# talking_train.net
KiCad netlist of a schematic drawn in EasyEDA Pro
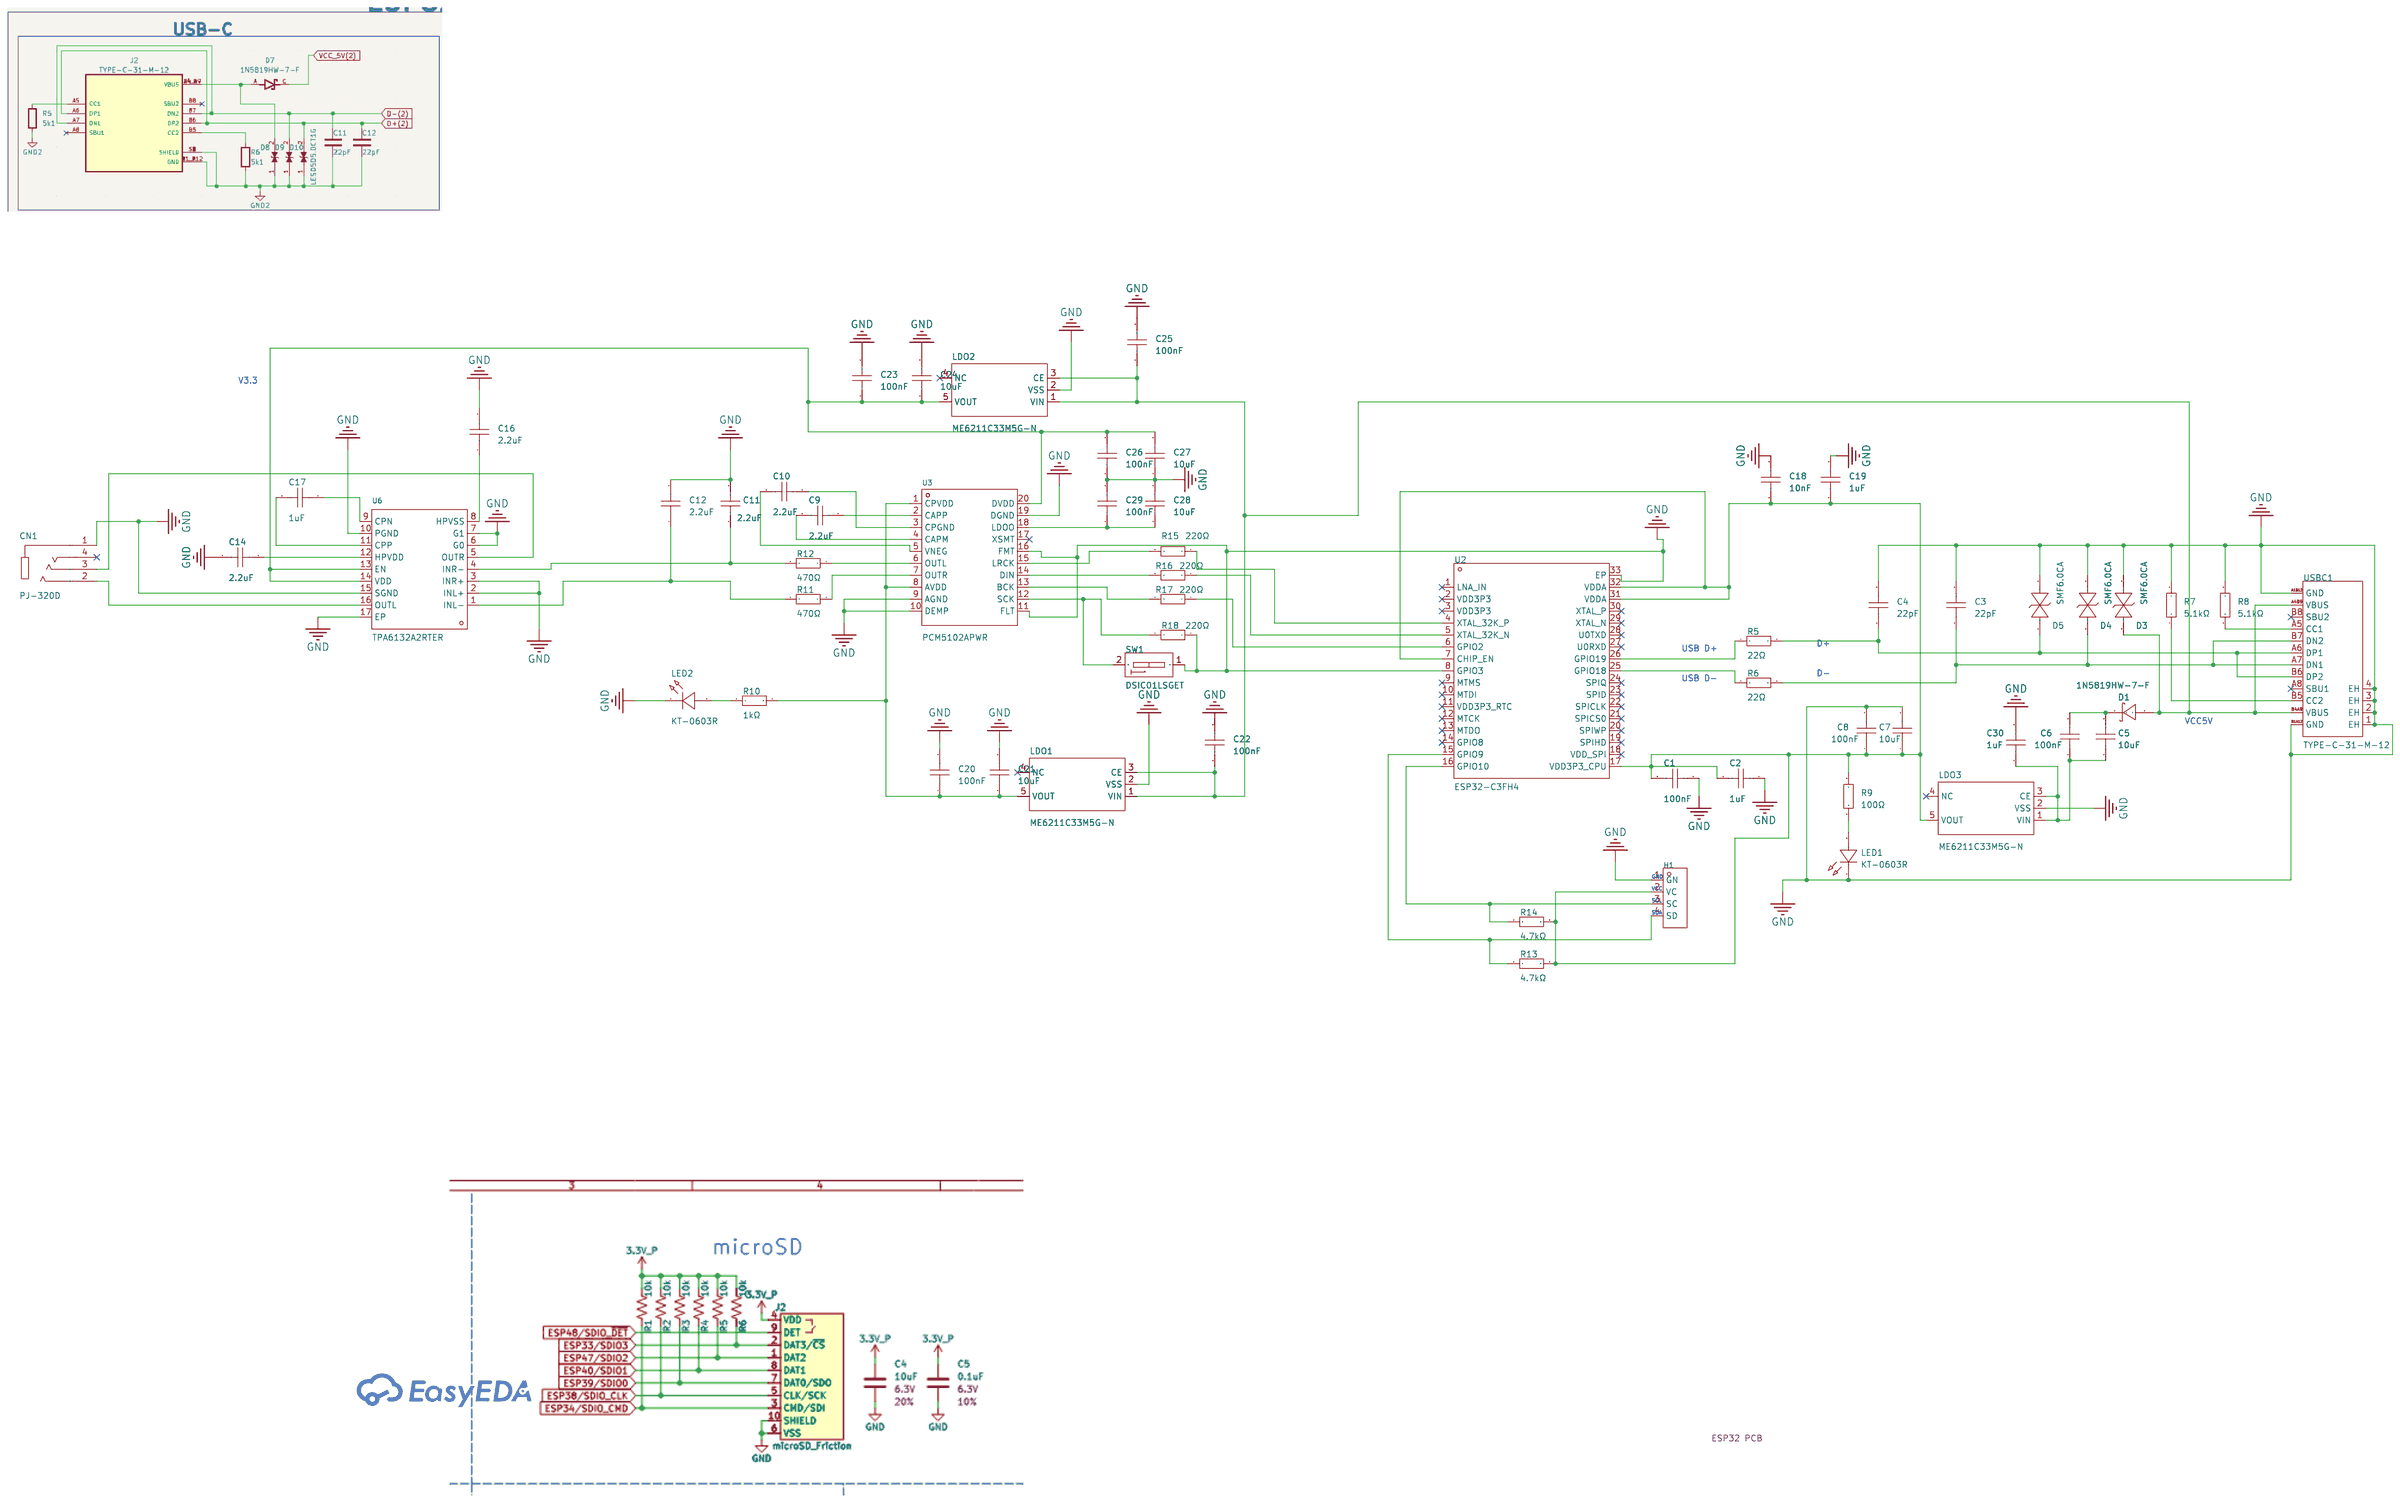
[diagram p0: schematic sheet]

(export (version "E")
  (design (tool "Eeschema 10.0.6"))
  (components
    (comp (ref "C1")
      (value "100nF")
      (footprint "easyedapro:C0603")
      (description "Capacitance:100nF Tolerance:±10% Tolerance:±10% Voltage Rating:50V Temperature Coefficient:X7R")
      (fields
        (field (name "Manufacturer Part") "CC0603KRX7R9BB104")
        (field (name "Manufacturer") "YAGEO(国巨)")
      )
      (libsource (lib "easyedapro") (part "CAP"))
    )
    (comp (ref "C2")
      (value "1uF")
      (footprint "easyedapro:C0603")
      (description "Capacitance:1uF Tolerance:±10% Tolerance:±10% Voltage Rating:50V Temperature Coefficient:X5R")
      (fields
        (field (name "Manufacturer Part") "CL10A105KB8NNNC")
        (field (name "Manufacturer") "SAMSUNG(三星)")
      )
      (libsource (lib "easyedapro") (part "CAP"))
    )
    (comp (ref "C3")
      (value "22pF")
      (footprint "easyedapro:C0603")
      (description "Capacitance:22pF Tolerance:±5% Tolerance:±5% Voltage Rating:50V Temperature Coefficient:C0G")
      (fields
        (field (name "Manufacturer Part") "CL10C220JB8NNNC")
        (field (name "Manufacturer") "SAMSUNG(三星)")
      )
      (libsource (lib "easyedapro") (part "CAP"))
    )
    (comp (ref "C4")
      (value "22pF")
      (footprint "easyedapro:C0603")
      (description "Capacitance:22pF Tolerance:±5% Tolerance:±5% Voltage Rating:50V Temperature Coefficient:C0G")
      (fields
        (field (name "Manufacturer Part") "CL10C220JB8NNNC")
        (field (name "Manufacturer") "SAMSUNG(三星)")
      )
      (libsource (lib "easyedapro") (part "CAP"))
    )
    (comp (ref "C5")
      (value "10uF")
      (footprint "easyedapro:C0603")
      (description "Capacitance:10uF Tolerance:±10% Tolerance:±10% Voltage Rating:10V Temperature Coefficient:X5R")
      (fields
        (field (name "Manufacturer Part") "CL10A106KP8NNNC")
        (field (name "Manufacturer") "SAMSUNG(三星)")
      )
      (libsource (lib "easyedapro") (part "CAP"))
    )
    (comp (ref "C6")
      (value "100nF")
      (footprint "easyedapro:C0603")
      (description "Capacitance:100nF Tolerance:±10% Tolerance:±10% Voltage Rating:50V Temperature Coefficient:X7R")
      (fields
        (field (name "Manufacturer Part") "CC0603KRX7R9BB104")
        (field (name "Manufacturer") "YAGEO(国巨)")
      )
      (libsource (lib "easyedapro") (part "CAP"))
    )
    (comp (ref "C7")
      (value "10uF")
      (footprint "easyedapro:C0603")
      (description "Capacitance:10uF Tolerance:±10% Tolerance:±10% Voltage Rating:10V Temperature Coefficient:X5R")
      (fields
        (field (name "Manufacturer Part") "CL10A106KP8NNNC")
        (field (name "Manufacturer") "SAMSUNG(三星)")
      )
      (libsource (lib "easyedapro") (part "CAP"))
    )
    (comp (ref "C8")
      (value "100nF")
      (footprint "easyedapro:C0603")
      (description "Capacitance:100nF Tolerance:±10% Tolerance:±10% Voltage Rating:50V Temperature Coefficient:X7R")
      (fields
        (field (name "Manufacturer Part") "CC0603KRX7R9BB104")
        (field (name "Manufacturer") "YAGEO(国巨)")
      )
      (libsource (lib "easyedapro") (part "CAP"))
    )
    (comp (ref "C9")
      (value "2.2uF")
      (footprint "easyedapro:C0603")
      (description "Capacitance:2.2uF Tolerance:±10% Tolerance:±10% Voltage Rating:16V Temperature Coefficient:X5R")
      (fields
        (field (name "Manufacturer Part") "CL10A225KO8NNNC")
        (field (name "Manufacturer") "SAMSUNG(三星)")
      )
      (libsource (lib "easyedapro") (part "CAP"))
    )
    (comp (ref "C10")
      (value "2.2uF")
      (footprint "easyedapro:C0603")
      (description "Capacitance:2.2uF Tolerance:±10% Tolerance:±10% Voltage Rating:16V Temperature Coefficient:X5R")
      (fields
        (field (name "Manufacturer Part") "CL10A225KO8NNNC")
        (field (name "Manufacturer") "SAMSUNG(三星)")
      )
      (libsource (lib "easyedapro") (part "CAP"))
    )
    (comp (ref "C11")
      (value "2.2uF")
      (footprint "easyedapro:C0603")
      (description "Capacitance:2.2uF Tolerance:±10% Tolerance:±10% Voltage Rating:16V Temperature Coefficient:X5R")
      (fields
        (field (name "Manufacturer Part") "CL10A225KO8NNNC")
        (field (name "Manufacturer") "SAMSUNG(三星)")
      )
      (libsource (lib "easyedapro") (part "CAP"))
    )
    (comp (ref "C12")
      (value "2.2uF")
      (footprint "easyedapro:C0603")
      (description "Capacitance:2.2uF Tolerance:±10% Tolerance:±10% Voltage Rating:16V Temperature Coefficient:X5R")
      (fields
        (field (name "Manufacturer Part") "CL10A225KO8NNNC")
        (field (name "Manufacturer") "SAMSUNG(三星)")
      )
      (libsource (lib "easyedapro") (part "CAP"))
    )
    (comp (ref "C14")
      (value "2.2uF")
      (footprint "easyedapro:C0603")
      (description "Capacitance:2.2uF Tolerance:±10% Tolerance:±10% Voltage Rating:16V Temperature Coefficient:X5R")
      (fields
        (field (name "Manufacturer Part") "CL10A225KO8NNNC")
        (field (name "Manufacturer") "SAMSUNG(三星)")
      )
      (libsource (lib "easyedapro") (part "CAP"))
    )
    (comp (ref "C16")
      (value "2.2uF")
      (footprint "easyedapro:C0603")
      (description "Capacitance:2.2uF Tolerance:±10% Tolerance:±10% Voltage Rating:16V Temperature Coefficient:X5R")
      (fields
        (field (name "Manufacturer Part") "CL10A225KO8NNNC")
        (field (name "Manufacturer") "SAMSUNG(三星)")
      )
      (libsource (lib "easyedapro") (part "CAP"))
    )
    (comp (ref "C17")
      (value "1uF")
      (footprint "easyedapro:C0603")
      (description "Capacitance:1uF Tolerance:±10% Tolerance:±10% Voltage Rating:50V Temperature Coefficient:X5R")
      (fields
        (field (name "Manufacturer Part") "CL10A105KB8NNNC")
        (field (name "Manufacturer") "SAMSUNG(三星)")
      )
      (libsource (lib "easyedapro") (part "CAP"))
    )
    (comp (ref "C18")
      (value "10nF")
      (footprint "easyedapro:C0603")
      (description "Capacitance:10nF Tolerance:±10% Tolerance:±10% Voltage Rating:50V Temperature Coefficient:X7R")
      (fields (field (name "Manufacturer Part") "0603B103K500NT") (field (name "Manufacturer") "FH(风华)"))
      (libsource (lib "easyedapro") (part "CAP"))
    )
    (comp (ref "C19")
      (value "1uF")
      (footprint "easyedapro:C0603")
      (description "Capacitance:1uF Tolerance:±10% Tolerance:±10% Voltage Rating:50V Temperature Coefficient:X5R")
      (fields
        (field (name "Manufacturer Part") "CL10A105KB8NNNC")
        (field (name "Manufacturer") "SAMSUNG(三星)")
      )
      (libsource (lib "easyedapro") (part "CAP"))
    )
    (comp (ref "C20")
      (value "100nF")
      (footprint "easyedapro:C0603")
      (description "Capacitance:100nF Tolerance:±10% Tolerance:±10% Voltage Rating:50V Temperature Coefficient:X7R")
      (fields
        (field (name "Manufacturer Part") "CC0603KRX7R9BB104")
        (field (name "Manufacturer") "YAGEO(国巨)")
      )
      (libsource (lib "easyedapro") (part "CAP"))
    )
    (comp (ref "C21")
      (value "10uF")
      (footprint "easyedapro:C0603")
      (description "Capacitance:10uF Tolerance:±10% Tolerance:±10% Voltage Rating:10V Temperature Coefficient:X5R")
      (fields
        (field (name "Manufacturer Part") "CL10A106KP8NNNC")
        (field (name "Manufacturer") "SAMSUNG(三星)")
      )
      (libsource (lib "easyedapro") (part "CAP"))
    )
    (comp (ref "C22")
      (value "100nF")
      (footprint "easyedapro:C0603")
      (description "Capacitance:100nF Tolerance:±10% Tolerance:±10% Voltage Rating:50V Temperature Coefficient:X7R")
      (fields
        (field (name "Manufacturer Part") "CC0603KRX7R9BB104")
        (field (name "Manufacturer") "YAGEO(国巨)")
      )
      (libsource (lib "easyedapro") (part "CAP"))
    )
    (comp (ref "C23")
      (value "100nF")
      (footprint "easyedapro:C0603")
      (description "Capacitance:100nF Tolerance:±10% Tolerance:±10% Voltage Rating:50V Temperature Coefficient:X7R")
      (fields
        (field (name "Manufacturer Part") "CC0603KRX7R9BB104")
        (field (name "Manufacturer") "YAGEO(国巨)")
      )
      (libsource (lib "easyedapro") (part "CAP"))
    )
    (comp (ref "C24")
      (value "10uF")
      (footprint "easyedapro:C0603")
      (description "Capacitance:10uF Tolerance:±10% Tolerance:±10% Voltage Rating:10V Temperature Coefficient:X5R")
      (fields
        (field (name "Manufacturer Part") "CL10A106KP8NNNC")
        (field (name "Manufacturer") "SAMSUNG(三星)")
      )
      (libsource (lib "easyedapro") (part "CAP"))
    )
    (comp (ref "C25")
      (value "100nF")
      (footprint "easyedapro:C0603")
      (description "Capacitance:100nF Tolerance:±10% Tolerance:±10% Voltage Rating:50V Temperature Coefficient:X7R")
      (fields
        (field (name "Manufacturer Part") "CC0603KRX7R9BB104")
        (field (name "Manufacturer") "YAGEO(国巨)")
      )
      (libsource (lib "easyedapro") (part "CAP"))
    )
    (comp (ref "C26")
      (value "100nF")
      (footprint "easyedapro:C0603")
      (description "Capacitance:100nF Tolerance:±10% Tolerance:±10% Voltage Rating:50V Temperature Coefficient:X7R")
      (fields
        (field (name "Manufacturer Part") "CC0603KRX7R9BB104")
        (field (name "Manufacturer") "YAGEO(国巨)")
      )
      (libsource (lib "easyedapro") (part "CAP"))
    )
    (comp (ref "C27")
      (value "10uF")
      (footprint "easyedapro:C0603")
      (description "Capacitance:10uF Tolerance:±10% Tolerance:±10% Voltage Rating:10V Temperature Coefficient:X5R")
      (fields
        (field (name "Manufacturer Part") "CL10A106KP8NNNC")
        (field (name "Manufacturer") "SAMSUNG(三星)")
      )
      (libsource (lib "easyedapro") (part "CAP"))
    )
    (comp (ref "C28")
      (value "10uF")
      (footprint "easyedapro:C0603")
      (description "Capacitance:10uF Tolerance:±10% Tolerance:±10% Voltage Rating:10V Temperature Coefficient:X5R")
      (fields
        (field (name "Manufacturer Part") "CL10A106KP8NNNC")
        (field (name "Manufacturer") "SAMSUNG(三星)")
      )
      (libsource (lib "easyedapro") (part "CAP"))
    )
    (comp (ref "C29")
      (value "100nF")
      (footprint "easyedapro:C0603")
      (description "Capacitance:100nF Tolerance:±10% Tolerance:±10% Voltage Rating:50V Temperature Coefficient:X7R")
      (fields
        (field (name "Manufacturer Part") "CC0603KRX7R9BB104")
        (field (name "Manufacturer") "YAGEO(国巨)")
      )
      (libsource (lib "easyedapro") (part "CAP"))
    )
    (comp (ref "C30")
      (value "1uF")
      (footprint "easyedapro:C0603")
      (description "Capacitance:1uF Tolerance:±10% Tolerance:±10% Voltage Rating:50V Temperature Coefficient:X7R")
      (fields
        (field (name "Manufacturer Part") "CL31B105KBHNNNE")
        (field (name "Manufacturer") "SAMSUNG(三星)")
      )
      (libsource (lib "easyedapro") (part "CAP"))
    )
    (comp (ref "CN1")
      (value "PJ-320D")
      (footprint "easyedapro:AUDIO-SMD_PJ-320D-1")
      (fields (field (name "Manufacturer") "SHOU HAN(首韩)"))
      (libsource (lib "easyedapro") (part "PJ-320D"))
    )
    (comp (ref "D1")
      (value "1N5819HW-7-F")
      (footprint "easyedapro:SOD-123_L2.7-W1.6-LS3.7-RD")
      (fields (field (name "Manufacturer") "DIODES(美台)"))
      (libsource (lib "easyedapro") (part "1N5819HW-7-F"))
    )
    (comp (ref "D3")
      (value "SMF6.0CA")
      (footprint "easyedapro:SOD-123FL_L2.7-W1.8-LS3.8-BI")
      (fields (field (name "Manufacturer") "R+O(宏嘉诚)"))
      (libsource (lib "easyedapro") (part "SMF6.0CA_C19077500"))
    )
    (comp (ref "D4")
      (value "SMF6.0CA")
      (footprint "easyedapro:SOD-123FL_L2.7-W1.8-LS3.8-BI")
      (fields (field (name "Manufacturer") "R+O(宏嘉诚)"))
      (libsource (lib "easyedapro") (part "SMF6.0CA_C19077500"))
    )
    (comp (ref "D5")
      (value "SMF6.0CA")
      (footprint "easyedapro:SOD-123FL_L2.7-W1.8-LS3.8-BI")
      (fields (field (name "Manufacturer") "R+O(宏嘉诚)"))
      (libsource (lib "easyedapro") (part "SMF6.0CA_C19077500"))
    )
    (comp (ref "H1")
      (value "2.54-1*4P母")
      (footprint "easyedapro:HDR-TH_4P-P2.54-V-F")
      (fields (field (name "Manufacturer") "BOOMELE(博穆精密)"))
      (libsource (lib "easyedapro") (part "2.54-1*4P母"))
    )
    (comp (ref "LDO1")
      (value "ME6211C33M5G-N")
      (footprint "easyedapro:SOT-23-5_L3.0-W1.7-P0.95-LS2.8-BL")
      (fields (field (name "Manufacturer") "MICRONE(南京微盟)"))
      (libsource (lib "easyedapro") (part "ME6211C33M5G-N"))
    )
    (comp (ref "LDO2")
      (value "ME6211C33M5G-N")
      (footprint "easyedapro:SOT-23-5_L3.0-W1.7-P0.95-LS2.8-BL")
      (fields (field (name "Manufacturer") "MICRONE(南京微盟)"))
      (libsource (lib "easyedapro") (part "ME6211C33M5G-N"))
    )
    (comp (ref "LDO3")
      (value "ME6211C33M5G-N")
      (footprint "easyedapro:SOT-23-5_L3.0-W1.7-P0.95-LS2.8-BL")
      (fields (field (name "Manufacturer") "MICRONE(南京微盟)"))
      (libsource (lib "easyedapro") (part "ME6211C33M5G-N"))
    )
    (comp (ref "LED1")
      (value "KT-0603R")
      (footprint "easyedapro:LED0603-RD_RED")
      (fields (field (name "Manufacturer") "KENTO"))
      (libsource (lib "easyedapro") (part "XL-1608SURC-06"))
    )
    (comp (ref "LED2")
      (value "KT-0603R")
      (footprint "easyedapro:LED0603-RD_RED")
      (fields (field (name "Manufacturer") "KENTO"))
      (libsource (lib "easyedapro") (part "XL-1608SURC-06"))
    )
    (comp (ref "R5")
      (value "22Ω")
      (footprint "easyedapro:R0603")
      (fields
        (field (name "Manufacturer Part") "0603WAF220JT5E")
        (field (name "Manufacturer") "UNI-ROYAL(厚声)")
      )
      (libsource (lib "easyedapro") (part "Res"))
    )
    (comp (ref "R6")
      (value "22Ω")
      (footprint "easyedapro:R0603")
      (fields
        (field (name "Manufacturer Part") "0603WAF220JT5E")
        (field (name "Manufacturer") "UNI-ROYAL(厚声)")
      )
      (libsource (lib "easyedapro") (part "Res"))
    )
    (comp (ref "R7")
      (value "5.1kΩ")
      (footprint "easyedapro:R0603")
      (fields
        (field (name "Manufacturer Part") "0805W8F5101T5E")
        (field (name "Manufacturer") "UNI-ROYAL(厚声)")
      )
      (libsource (lib "easyedapro") (part "Res"))
    )
    (comp (ref "R8")
      (value "5.1kΩ")
      (footprint "easyedapro:R0603")
      (fields
        (field (name "Manufacturer Part") "0805W8F5101T5E")
        (field (name "Manufacturer") "UNI-ROYAL(厚声)")
      )
      (libsource (lib "easyedapro") (part "Res"))
    )
    (comp (ref "R9")
      (value "100Ω")
      (footprint "easyedapro:R0603")
      (fields
        (field (name "Manufacturer Part") "0603WAF1000T5E")
        (field (name "Manufacturer") "UNI-ROYAL(厚声)")
      )
      (libsource (lib "easyedapro") (part "Res"))
    )
    (comp (ref "R10")
      (value "1kΩ")
      (footprint "easyedapro:R0603")
      (fields
        (field (name "Manufacturer Part") "0603WAF1001T5E")
        (field (name "Manufacturer") "UNI-ROYAL(厚声)")
      )
      (libsource (lib "easyedapro") (part "Res"))
    )
    (comp (ref "R11")
      (value "470Ω")
      (footprint "easyedapro:R0603")
      (fields
        (field (name "Manufacturer Part") "0603WAF4700T5E")
        (field (name "Manufacturer") "UNI-ROYAL(厚声)")
      )
      (libsource (lib "easyedapro") (part "Res"))
    )
    (comp (ref "R12")
      (value "470Ω")
      (footprint "easyedapro:R0603")
      (fields
        (field (name "Manufacturer Part") "0603WAF4700T5E")
        (field (name "Manufacturer") "UNI-ROYAL(厚声)")
      )
      (libsource (lib "easyedapro") (part "Res"))
    )
    (comp (ref "R13")
      (value "4.7kΩ")
      (footprint "easyedapro:R0603")
      (fields
        (field (name "Manufacturer Part") "0603WAF4701T5E")
        (field (name "Manufacturer") "UNI-ROYAL(厚声)")
      )
      (libsource (lib "easyedapro") (part "Res"))
    )
    (comp (ref "R14")
      (value "4.7kΩ")
      (footprint "easyedapro:R0603")
      (fields
        (field (name "Manufacturer Part") "0603WAF4701T5E")
        (field (name "Manufacturer") "UNI-ROYAL(厚声)")
      )
      (libsource (lib "easyedapro") (part "Res"))
    )
    (comp (ref "R15")
      (value "220Ω")
      (footprint "easyedapro:R0603")
      (fields
        (field (name "Manufacturer Part") "0603WAF2200T5E")
        (field (name "Manufacturer") "UNI-ROYAL(厚声)")
      )
      (libsource (lib "easyedapro") (part "Res"))
    )
    (comp (ref "R16")
      (value "220Ω")
      (footprint "easyedapro:R0603")
      (fields
        (field (name "Manufacturer Part") "0603WAF2200T5E")
        (field (name "Manufacturer") "UNI-ROYAL(厚声)")
      )
      (libsource (lib "easyedapro") (part "Res"))
    )
    (comp (ref "R17")
      (value "220Ω")
      (footprint "easyedapro:R0603")
      (fields
        (field (name "Manufacturer Part") "0603WAF2200T5E")
        (field (name "Manufacturer") "UNI-ROYAL(厚声)")
      )
      (libsource (lib "easyedapro") (part "Res"))
    )
    (comp (ref "R18")
      (value "220Ω")
      (footprint "easyedapro:R0603")
      (fields
        (field (name "Manufacturer Part") "0603WAF2200T5E")
        (field (name "Manufacturer") "UNI-ROYAL(厚声)")
      )
      (libsource (lib "easyedapro") (part "Res"))
    )
    (comp (ref "SW1")
      (value "DSIC01LSGET")
      (footprint "easyedapro:SW-SMD_DSIC01LSGET")
      (description "Type:Slide, Rocked Circuit:SPST Number of Positions:1 Lead Pitch:- Operating Life:- Color:Black")
      (fields (field (name "Manufacturer") "YE"))
      (libsource (lib "easyedapro") (part "DSIC01LSGET"))
    )
    (comp (ref "U2")
      (value "ESP32-C3FH4")
      (footprint "easyedapro:QFN-32_L5.0-W5.0-P0.50-TL-EP3.7")
      (fields (field (name "Manufacturer") "ESPRESSIF(乐鑫)"))
      (libsource (lib "easyedapro") (part "ESP32-C3FH4"))
    )
    (comp (ref "U3")
      (value "PCM5102APWR")
      (footprint "easyedapro:TSSOP-20_L6.5-W4.4-P0.65-LS6.4-BL")
      (fields (field (name "Manufacturer") "TI(德州仪器)"))
      (libsource (lib "easyedapro") (part "PCM5102APWR"))
    )
    (comp (ref "U6")
      (value "TPA6132A2RTER")
      (footprint "easyedapro:WQFN-16_L3.0-W3.0-P0.50-TL-EP1.6")
      (fields (field (name "Manufacturer") "TI(德州仪器)"))
      (libsource (lib "easyedapro") (part "TPA6132A2RTER"))
    )
    (comp (ref "USBC1")
      (value "TYPE-C-31-M-12")
      (footprint "easyedapro:USB-C_SMD-TYPE-C-31-M-12_1")
      (fields (field (name "Manufacturer") "韩国韩荣"))
      (libsource (lib "easyedapro") (part "TYPE-C-31-M-12"))
    )
  )
  (nets
    (net (code "1") (name "GND") (class "Default")
      (node (ref "C1") (pin "1") (pinfunction "1_1") (pintype "input"))
      (node (ref "C11") (pin "2") (pinfunction "2_2") (pintype "input"))
      (node (ref "C12") (pin "2") (pinfunction "2_2") (pintype "input"))
      (node (ref "C14") (pin "1") (pinfunction "1_1") (pintype "input"))
      (node (ref "C16") (pin "2") (pinfunction "2_2") (pintype "input"))
      (node (ref "C18") (pin "1") (pinfunction "1_1") (pintype "input"))
      (node (ref "C19") (pin "1") (pinfunction "1_1") (pintype "input"))
      (node (ref "C2") (pin "1") (pinfunction "1_1") (pintype "input"))
      (node (ref "C20") (pin "2") (pinfunction "2_2") (pintype "input"))
      (node (ref "C21") (pin "2") (pinfunction "2_2") (pintype "input"))
      (node (ref "C22") (pin "2") (pinfunction "2_2") (pintype "input"))
      (node (ref "C23") (pin "2") (pinfunction "2_2") (pintype "input"))
      (node (ref "C24") (pin "2") (pinfunction "2_2") (pintype "input"))
      (node (ref "C25") (pin "2") (pinfunction "2_2") (pintype "input"))
      (node (ref "C26") (pin "1") (pinfunction "1_1") (pintype "input"))
      (node (ref "C27") (pin "1") (pinfunction "1_1") (pintype "input"))
      (node (ref "C28") (pin "2") (pinfunction "2_2") (pintype "input"))
      (node (ref "C29") (pin "2") (pinfunction "2_2") (pintype "input"))
      (node (ref "C3") (pin "2") (pinfunction "2_2") (pintype "input"))
      (node (ref "C30") (pin "2") (pinfunction "2_2") (pintype "input"))
      (node (ref "C4") (pin "2") (pinfunction "2_2") (pintype "input"))
      (node (ref "C7") (pin "2") (pinfunction "2_2") (pintype "input"))
      (node (ref "C8") (pin "2") (pinfunction "2_2") (pintype "input"))
      (node (ref "CN1") (pin "1") (pinfunction "1_1") (pintype "unspecified"))
      (node (ref "D3") (pin "1") (pinfunction "1_1") (pintype "unspecified"))
      (node (ref "D4") (pin "1") (pinfunction "1_1") (pintype "unspecified"))
      (node (ref "D5") (pin "1") (pinfunction "1_1") (pintype "unspecified"))
      (node (ref "H1") (pin "1") (pinfunction "GN_1") (pintype "input"))
      (node (ref "LDO1") (pin "2") (pinfunction "VSS_2") (pintype "unspecified"))
      (node (ref "LDO2") (pin "2") (pinfunction "VSS_2") (pintype "unspecified"))
      (node (ref "LDO3") (pin "2") (pinfunction "VSS_2") (pintype "unspecified"))
      (node (ref "LED1") (pin "1") (pinfunction "K_1") (pintype "unspecified"))
      (node (ref "LED2") (pin "1") (pinfunction "K_1") (pintype "unspecified"))
      (node (ref "R18") (pin "1") (pinfunction "1_1") (pintype "input"))
      (node (ref "R7") (pin "2") (pinfunction "2_2") (pintype "input"))
      (node (ref "R8") (pin "2") (pinfunction "2_2") (pintype "input"))
      (node (ref "SW1") (pin "1") (pinfunction "A1_1") (pintype "input"))
      (node (ref "U2") (pin "33") (pinfunction "EP_33") (pintype "unspecified"))
      (node (ref "U2") (pin "8") (pinfunction "GPIO3_8") (pintype "unspecified"))
      (node (ref "U3") (pin "10") (pinfunction "DEMP_10") (pintype "input"))
      (node (ref "U3") (pin "11") (pinfunction "FLT_11") (pintype "input"))
      (node (ref "U3") (pin "16") (pinfunction "FMT_16") (pintype "input"))
      (node (ref "U3") (pin "19") (pinfunction "DGND_19") (pintype "input"))
      (node (ref "U3") (pin "9") (pinfunction "AGND_9") (pintype "input"))
      (node (ref "U6") (pin "10") (pinfunction "PGND_10") (pintype "input"))
      (node (ref "U6") (pin "15") (pinfunction "SGND_15") (pintype "input"))
      (node (ref "U6") (pin "17") (pinfunction "EP_17") (pintype "input"))
      (node (ref "U6") (pin "2") (pinfunction "INL+_2") (pintype "input"))
      (node (ref "U6") (pin "3") (pinfunction "INR+_3") (pintype "input"))
      (node (ref "U6") (pin "6") (pinfunction "G0_6") (pintype "input"))
      (node (ref "U6") (pin "7") (pinfunction "G1_7") (pintype "input"))
      (node (ref "USBC1") (pin "1") (pinfunction "EH_1") (pintype "unspecified"))
      (node (ref "USBC1") (pin "2") (pinfunction "EH_2") (pintype "unspecified"))
      (node (ref "USBC1") (pin "3") (pinfunction "EH_3") (pintype "unspecified"))
      (node (ref "USBC1") (pin "4") (pinfunction "EH_4") (pintype "unspecified"))
      (node (ref "USBC1") (pin "A1B12") (pinfunction "GND_A1B12") (pintype "unspecified"))
      (node (ref "USBC1") (pin "B1A12") (pinfunction "GND_B1A12") (pintype "unspecified"))
    )
    (net (code "2") (name "Net-(D1-A)") (class "Default")
      (node (ref "C22") (pin "1") (pinfunction "1_1") (pintype "input"))
      (node (ref "C25") (pin "1") (pinfunction "1_1") (pintype "input"))
      (node (ref "D1") (pin "2") (pinfunction "A_2") (pintype "unspecified"))
      (node (ref "D3") (pin "2") (pinfunction "2_2") (pintype "unspecified"))
      (node (ref "LDO1") (pin "1") (pinfunction "VIN_1") (pintype "unspecified"))
      (node (ref "LDO1") (pin "3") (pinfunction "CE_3") (pintype "unspecified"))
      (node (ref "LDO2") (pin "1") (pinfunction "VIN_1") (pintype "unspecified"))
      (node (ref "LDO2") (pin "3") (pinfunction "CE_3") (pintype "unspecified"))
      (node (ref "USBC1") (pin "A4B9") (pinfunction "VBUS_A4B9") (pintype "unspecified"))
      (node (ref "USBC1") (pin "B4A9") (pinfunction "VBUS_B4A9") (pintype "unspecified"))
    )
    (net (code "3") (name "Net-(D1-K)") (class "Default")
      (node (ref "C5") (pin "2") (pinfunction "2_2") (pintype "input"))
      (node (ref "C6") (pin "2") (pinfunction "2_2") (pintype "input"))
      (node (ref "D1") (pin "1") (pinfunction "K_1") (pintype "unspecified"))
    )
    (net (code "4") (name "Net-(H1-SC)") (class "Default")
      (node (ref "H1") (pin "3") (pinfunction "SC_3") (pintype "input"))
      (node (ref "R14") (pin "1") (pinfunction "1_1") (pintype "input"))
      (node (ref "U2") (pin "16") (pinfunction "GPIO10_16") (pintype "unspecified"))
    )
    (net (code "5") (name "Net-(H1-SD)") (class "Default")
      (node (ref "H1") (pin "4") (pinfunction "SD_4") (pintype "input"))
      (node (ref "R13") (pin "1") (pinfunction "1_1") (pintype "input"))
      (node (ref "U2") (pin "15") (pinfunction "GPIO9_15") (pintype "unspecified"))
    )
    (net (code "6") (name "Net-(H1-VC)") (class "Default")
      (node (ref "C1") (pin "2") (pinfunction "2_2") (pintype "input"))
      (node (ref "C18") (pin "2") (pinfunction "2_2") (pintype "input"))
      (node (ref "C19") (pin "2") (pinfunction "2_2") (pintype "input"))
      (node (ref "C2") (pin "2") (pinfunction "2_2") (pintype "input"))
      (node (ref "C7") (pin "1") (pinfunction "1_1") (pintype "input"))
      (node (ref "C8") (pin "1") (pinfunction "1_1") (pintype "input"))
      (node (ref "H1") (pin "2") (pinfunction "VC_2") (pintype "input"))
      (node (ref "LDO3") (pin "5") (pinfunction "VOUT_5") (pintype "unspecified"))
      (node (ref "R13") (pin "2") (pinfunction "2_2") (pintype "input"))
      (node (ref "R14") (pin "2") (pinfunction "2_2") (pintype "input"))
      (node (ref "R9") (pin "2") (pinfunction "2_2") (pintype "input"))
      (node (ref "U2") (pin "17") (pinfunction "VDD3P3_CPU_17") (pintype "unspecified"))
      (node (ref "U2") (pin "31") (pinfunction "VDDA_31") (pintype "unspecified"))
      (node (ref "U2") (pin "32") (pinfunction "VDDA_32") (pintype "unspecified"))
      (node (ref "U2") (pin "7") (pinfunction "CHIP_EN_7") (pintype "unspecified"))
    )
    (net (code "7") (name "Net-(LDO1-VOUT)") (class "Default")
      (node (ref "C20") (pin "1") (pinfunction "1_1") (pintype "input"))
      (node (ref "C21") (pin "1") (pinfunction "1_1") (pintype "input"))
      (node (ref "LDO1") (pin "5") (pinfunction "VOUT_5") (pintype "unspecified"))
      (node (ref "R10") (pin "1") (pinfunction "1_1") (pintype "input"))
      (node (ref "U3") (pin "1") (pinfunction "CPVDD_1") (pintype "input"))
      (node (ref "U3") (pin "8") (pinfunction "AVDD_8") (pintype "input"))
    )
    (net (code "8") (name "Net-(LDO2-VOUT)") (class "Default")
      (node (ref "C23") (pin "1") (pinfunction "1_1") (pintype "input"))
      (node (ref "C24") (pin "1") (pinfunction "1_1") (pintype "input"))
      (node (ref "C26") (pin "2") (pinfunction "2_2") (pintype "input"))
      (node (ref "C27") (pin "2") (pinfunction "2_2") (pintype "input"))
      (node (ref "LDO2") (pin "5") (pinfunction "VOUT_5") (pintype "unspecified"))
      (node (ref "U3") (pin "20") (pinfunction "DVDD_20") (pintype "input"))
      (node (ref "U6") (pin "13") (pinfunction "EN_13") (pintype "input"))
      (node (ref "U6") (pin "14") (pinfunction "VDD_14") (pintype "input"))
    )
    (net (code "9") (name "Net-(LDO3-CE)") (class "Default")
      (node (ref "C30") (pin "1") (pinfunction "1_1") (pintype "input"))
      (node (ref "C5") (pin "1") (pinfunction "1_1") (pintype "input"))
      (node (ref "C6") (pin "1") (pinfunction "1_1") (pintype "input"))
      (node (ref "LDO3") (pin "1") (pinfunction "VIN_1") (pintype "unspecified"))
      (node (ref "LDO3") (pin "3") (pinfunction "CE_3") (pintype "unspecified"))
    )
    (net (code "10") (name "Net-(LED1-A)") (class "Default")
      (node (ref "LED1") (pin "2") (pinfunction "A_2") (pintype "unspecified"))
      (node (ref "R9") (pin "1") (pinfunction "1_1") (pintype "input"))
    )
    (net (code "11") (name "Net-(LED2-A)") (class "Default")
      (node (ref "LED2") (pin "2") (pinfunction "A_2") (pintype "unspecified"))
      (node (ref "R10") (pin "2") (pinfunction "2_2") (pintype "input"))
    )
    (net (code "12") (name "Net-(SW1-A2)") (class "Default")
      (node (ref "R18") (pin "2") (pinfunction "2_2") (pintype "input"))
      (node (ref "SW1") (pin "2") (pinfunction "A2_2") (pintype "input"))
      (node (ref "U3") (pin "12") (pinfunction "SCK_12") (pintype "input"))
    )
    (net (code "13") (name "Net-(U2-GPIO2)") (class "Default")
      (node (ref "R17") (pin "1") (pinfunction "1_1") (pintype "input"))
      (node (ref "U2") (pin "6") (pinfunction "GPIO2_6") (pintype "unspecified"))
    )
    (net (code "14") (name "Net-(U2-GPIO18)") (class "Default")
      (node (ref "R6") (pin "1") (pinfunction "1_1") (pintype "input"))
      (node (ref "U2") (pin "25") (pinfunction "GPIO18_25") (pintype "unspecified"))
    )
    (net (code "15") (name "Net-(U2-GPIO19)") (class "Default")
      (node (ref "R5") (pin "1") (pinfunction "1_1") (pintype "input"))
      (node (ref "U2") (pin "26") (pinfunction "GPIO19_26") (pintype "unspecified"))
    )
    (net (code "16") (name "Net-(U2-XTAL_32K_N)") (class "Default")
      (node (ref "R16") (pin "1") (pinfunction "1_1") (pintype "input"))
      (node (ref "U2") (pin "5") (pinfunction "XTAL_32K_N_5") (pintype "unspecified"))
    )
    (net (code "17") (name "Net-(U2-XTAL_32K_P)") (class "Default")
      (node (ref "R15") (pin "1") (pinfunction "1_1") (pintype "input"))
      (node (ref "U2") (pin "4") (pinfunction "XTAL_32K_P_4") (pintype "unspecified"))
    )
    (net (code "18") (name "Net-(U3-BCK)") (class "Default")
      (node (ref "R17") (pin "2") (pinfunction "2_2") (pintype "input"))
      (node (ref "U3") (pin "13") (pinfunction "BCK_13") (pintype "input"))
    )
    (net (code "19") (name "Net-(U3-CAPM)") (class "Default")
      (node (ref "C9") (pin "2") (pinfunction "2_2") (pintype "input"))
      (node (ref "U3") (pin "4") (pinfunction "CAPM_4") (pintype "input"))
    )
    (net (code "20") (name "Net-(U3-CAPP)") (class "Default")
      (node (ref "C9") (pin "1") (pinfunction "1_1") (pintype "input"))
      (node (ref "U3") (pin "2") (pinfunction "CAPP_2") (pintype "input"))
    )
    (net (code "21") (name "Net-(U3-CPGND)") (class "Default")
      (node (ref "C10") (pin "1") (pinfunction "1_1") (pintype "input"))
      (node (ref "U3") (pin "3") (pinfunction "CPGND_3") (pintype "input"))
    )
    (net (code "22") (name "Net-(U3-DIN)") (class "Default")
      (node (ref "R16") (pin "2") (pinfunction "2_2") (pintype "input"))
      (node (ref "U3") (pin "14") (pinfunction "DIN_14") (pintype "input"))
    )
    (net (code "23") (name "Net-(U3-LDOO)") (class "Default")
      (node (ref "C28") (pin "1") (pinfunction "1_1") (pintype "input"))
      (node (ref "C29") (pin "1") (pinfunction "1_1") (pintype "input"))
      (node (ref "U3") (pin "18") (pinfunction "LDOO_18") (pintype "input"))
    )
    (net (code "24") (name "Net-(U3-LRCK)") (class "Default")
      (node (ref "R15") (pin "2") (pinfunction "2_2") (pintype "input"))
      (node (ref "U3") (pin "15") (pinfunction "LRCK_15") (pintype "input"))
    )
    (net (code "25") (name "Net-(U3-OUTL)") (class "Default")
      (node (ref "R12") (pin "1") (pinfunction "1_1") (pintype "input"))
      (node (ref "U3") (pin "6") (pinfunction "OUTL_6") (pintype "input"))
    )
    (net (code "26") (name "Net-(U3-OUTR)") (class "Default")
      (node (ref "R11") (pin "1") (pinfunction "1_1") (pintype "input"))
      (node (ref "U3") (pin "7") (pinfunction "OUTR_7") (pintype "input"))
    )
    (net (code "27") (name "Net-(U3-VNEG)") (class "Default")
      (node (ref "C10") (pin "2") (pinfunction "2_2") (pintype "input"))
      (node (ref "U3") (pin "5") (pinfunction "VNEG_5") (pintype "input"))
    )
    (net (code "28") (name "Net-(U6-CPN)") (class "Default")
      (node (ref "C17") (pin "1") (pinfunction "1_1") (pintype "input"))
      (node (ref "U6") (pin "9") (pinfunction "CPN_9") (pintype "input"))
    )
    (net (code "29") (name "Net-(U6-CPP)") (class "Default")
      (node (ref "C17") (pin "2") (pinfunction "2_2") (pintype "input"))
      (node (ref "U6") (pin "11") (pinfunction "CPP_11") (pintype "input"))
    )
    (net (code "30") (name "Net-(U6-HPVDD)") (class "Default")
      (node (ref "C14") (pin "2") (pinfunction "2_2") (pintype "input"))
      (node (ref "U6") (pin "12") (pinfunction "HPVDD_12") (pintype "input"))
    )
    (net (code "31") (name "Net-(U6-HPVSS)") (class "Default")
      (node (ref "C16") (pin "1") (pinfunction "1_1") (pintype "input"))
      (node (ref "U6") (pin "8") (pinfunction "HPVSS_8") (pintype "input"))
    )
    (net (code "32") (name "Net-(U6-INL-)") (class "Default")
      (node (ref "C12") (pin "1") (pinfunction "1_1") (pintype "input"))
      (node (ref "R11") (pin "2") (pinfunction "2_2") (pintype "input"))
      (node (ref "U6") (pin "1") (pinfunction "INL-_1") (pintype "input"))
    )
    (net (code "33") (name "Net-(U6-INR-)") (class "Default")
      (node (ref "C11") (pin "1") (pinfunction "1_1") (pintype "input"))
      (node (ref "R12") (pin "2") (pinfunction "2_2") (pintype "input"))
      (node (ref "U6") (pin "4") (pinfunction "INR-_4") (pintype "input"))
    )
    (net (code "34") (name "Net-(U6-OUTL)") (class "Default")
      (node (ref "CN1") (pin "2") (pinfunction "2_2") (pintype "unspecified"))
      (node (ref "U6") (pin "16") (pinfunction "OUTL_16") (pintype "input"))
    )
    (net (code "35") (name "Net-(U6-OUTR)") (class "Default")
      (node (ref "CN1") (pin "3") (pinfunction "3_3") (pintype "unspecified"))
      (node (ref "U6") (pin "5") (pinfunction "OUTR_5") (pintype "input"))
    )
    (net (code "36") (name "Net-(USBC1-CC1)") (class "Default")
      (node (ref "R8") (pin "1") (pinfunction "1_1") (pintype "input"))
      (node (ref "USBC1") (pin "A5") (pinfunction "CC1_A5") (pintype "unspecified"))
    )
    (net (code "37") (name "Net-(USBC1-CC2)") (class "Default")
      (node (ref "R7") (pin "1") (pinfunction "1_1") (pintype "input"))
      (node (ref "USBC1") (pin "B5") (pinfunction "CC2_B5") (pintype "unspecified"))
    )
    (net (code "38") (name "Net-(USBC1-DN1)") (class "Default")
      (node (ref "C3") (pin "1") (pinfunction "1_1") (pintype "input"))
      (node (ref "D4") (pin "2") (pinfunction "2_2") (pintype "unspecified"))
      (node (ref "R6") (pin "2") (pinfunction "2_2") (pintype "input"))
      (node (ref "USBC1") (pin "A7") (pinfunction "DN1_A7") (pintype "unspecified"))
      (node (ref "USBC1") (pin "B7") (pinfunction "DN2_B7") (pintype "unspecified"))
    )
    (net (code "39") (name "Net-(USBC1-DP1)") (class "Default")
      (node (ref "C4") (pin "1") (pinfunction "1_1") (pintype "input"))
      (node (ref "D5") (pin "2") (pinfunction "2_2") (pintype "unspecified"))
      (node (ref "R5") (pin "2") (pinfunction "2_2") (pintype "input"))
      (node (ref "USBC1") (pin "A6") (pinfunction "DP1_A6") (pintype "unspecified"))
      (node (ref "USBC1") (pin "B6") (pinfunction "DP2_B6") (pintype "unspecified"))
    )
    (net (code "40") (name "unconnected-(CN1-Pad4)") (class "Default")
      (node (ref "CN1") (pin "4") (pinfunction "4_4") (pintype "unspecified+no_connect"))
    )
    (net (code "41") (name "unconnected-(LDO1-NC-Pad4)") (class "Default")
      (node (ref "LDO1") (pin "4") (pinfunction "NC_4") (pintype "unspecified+no_connect"))
    )
    (net (code "42") (name "unconnected-(LDO2-NC-Pad4)") (class "Default")
      (node (ref "LDO2") (pin "4") (pinfunction "NC_4") (pintype "unspecified+no_connect"))
    )
    (net (code "43") (name "unconnected-(LDO3-NC-Pad4)") (class "Default")
      (node (ref "LDO3") (pin "4") (pinfunction "NC_4") (pintype "unspecified+no_connect"))
    )
    (net (code "44") (name "unconnected-(U2-GPIO8-Pad14)") (class "Default")
      (node (ref "U2") (pin "14") (pinfunction "GPIO8_14") (pintype "unspecified+no_connect"))
    )
    (net (code "45") (name "unconnected-(U2-LNA_IN-Pad1)") (class "Default")
      (node (ref "U2") (pin "1") (pinfunction "LNA_IN_1") (pintype "unspecified+no_connect"))
    )
    (net (code "46") (name "unconnected-(U2-MTCK-Pad12)") (class "Default")
      (node (ref "U2") (pin "12") (pinfunction "MTCK_12") (pintype "unspecified+no_connect"))
    )
    (net (code "47") (name "unconnected-(U2-MTDI-Pad10)") (class "Default")
      (node (ref "U2") (pin "10") (pinfunction "MTDI_10") (pintype "unspecified+no_connect"))
    )
    (net (code "48") (name "unconnected-(U2-MTDO-Pad13)") (class "Default")
      (node (ref "U2") (pin "13") (pinfunction "MTDO_13") (pintype "unspecified+no_connect"))
    )
    (net (code "49") (name "unconnected-(U2-MTMS-Pad9)") (class "Default")
      (node (ref "U2") (pin "9") (pinfunction "MTMS_9") (pintype "unspecified+no_connect"))
    )
    (net (code "50") (name "unconnected-(U2-SPICLK-Pad22)") (class "Default")
      (node (ref "U2") (pin "22") (pinfunction "SPICLK_22") (pintype "unspecified+no_connect"))
    )
    (net (code "51") (name "unconnected-(U2-SPICS0-Pad21)") (class "Default")
      (node (ref "U2") (pin "21") (pinfunction "SPICS0_21") (pintype "unspecified+no_connect"))
    )
    (net (code "52") (name "unconnected-(U2-SPID-Pad23)") (class "Default")
      (node (ref "U2") (pin "23") (pinfunction "SPID_23") (pintype "unspecified+no_connect"))
    )
    (net (code "53") (name "unconnected-(U2-SPIHD-Pad19)") (class "Default")
      (node (ref "U2") (pin "19") (pinfunction "SPIHD_19") (pintype "unspecified+no_connect"))
    )
    (net (code "54") (name "unconnected-(U2-SPIQ-Pad24)") (class "Default")
      (node (ref "U2") (pin "24") (pinfunction "SPIQ_24") (pintype "unspecified+no_connect"))
    )
    (net (code "55") (name "unconnected-(U2-SPIWP-Pad20)") (class "Default")
      (node (ref "U2") (pin "20") (pinfunction "SPIWP_20") (pintype "unspecified+no_connect"))
    )
    (net (code "56") (name "unconnected-(U2-U0RXD-Pad27)") (class "Default")
      (node (ref "U2") (pin "27") (pinfunction "U0RXD_27") (pintype "unspecified+no_connect"))
    )
    (net (code "57") (name "unconnected-(U2-U0TXD-Pad28)") (class "Default")
      (node (ref "U2") (pin "28") (pinfunction "U0TXD_28") (pintype "unspecified+no_connect"))
    )
    (net (code "58") (name "unconnected-(U2-VDD3P3-Pad2)") (class "Default")
      (node (ref "U2") (pin "2") (pinfunction "VDD3P3_2") (pintype "unspecified+no_connect"))
    )
    (net (code "59") (name "unconnected-(U2-VDD3P3-Pad3)") (class "Default")
      (node (ref "U2") (pin "3") (pinfunction "VDD3P3_3") (pintype "unspecified+no_connect"))
    )
    (net (code "60") (name "unconnected-(U2-VDD3P3_RTC-Pad11)") (class "Default")
      (node (ref "U2") (pin "11") (pinfunction "VDD3P3_RTC_11") (pintype "unspecified+no_connect"))
    )
    (net (code "61") (name "unconnected-(U2-VDD_SPI-Pad18)") (class "Default")
      (node (ref "U2") (pin "18") (pinfunction "VDD_SPI_18") (pintype "unspecified+no_connect"))
    )
    (net (code "62") (name "unconnected-(U2-XTAL_N-Pad29)") (class "Default")
      (node (ref "U2") (pin "29") (pinfunction "XTAL_N_29") (pintype "unspecified+no_connect"))
    )
    (net (code "63") (name "unconnected-(U2-XTAL_P-Pad30)") (class "Default")
      (node (ref "U2") (pin "30") (pinfunction "XTAL_P_30") (pintype "unspecified+no_connect"))
    )
    (net (code "64") (name "unconnected-(U3-XSMT-Pad17)") (class "Default")
      (node (ref "U3") (pin "17") (pinfunction "XSMT_17") (pintype "input+no_connect"))
    )
    (net (code "65") (name "unconnected-(USBC1-SBU1-PadA8)") (class "Default")
      (node (ref "USBC1") (pin "A8") (pinfunction "SBU1_A8") (pintype "unspecified+no_connect"))
    )
    (net (code "66") (name "unconnected-(USBC1-SBU2-PadB8)") (class "Default")
      (node (ref "USBC1") (pin "B8") (pinfunction "SBU2_B8") (pintype "unspecified+no_connect"))
    )
  )
)
